# BareBones_Arduino_full_size.net
KiCad netlist of a schematic drawn in EAGLE
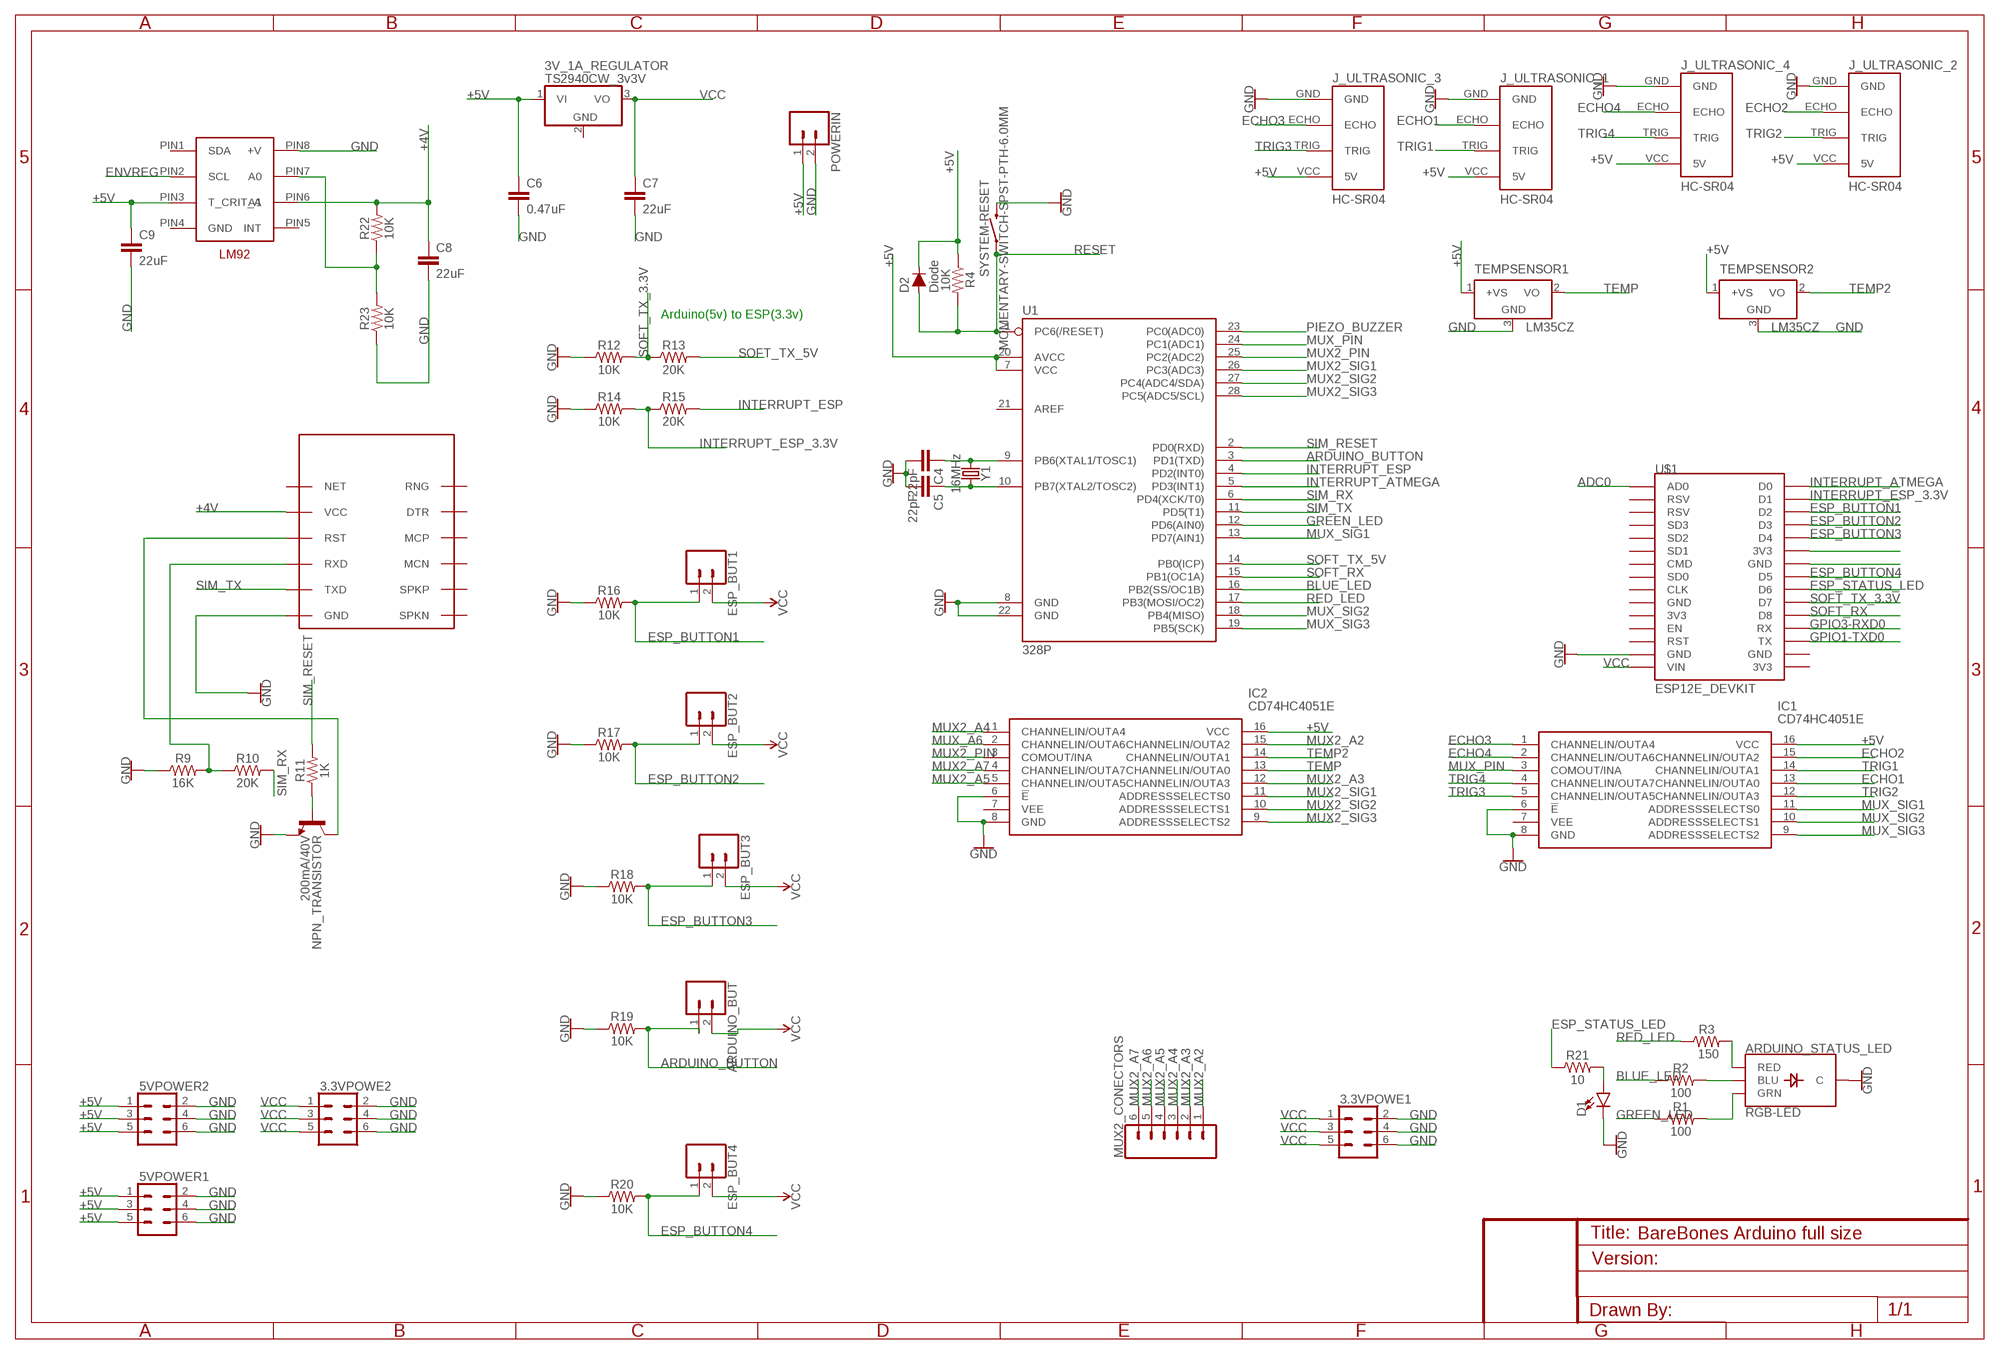
[diagram p0: schematic, sheet 1]

(export (version "E")
  (design (tool "Eeschema 10.0.6"))
  (components
    (comp (ref "3.3VPOWE1")
      (value "CONN_03X2FEMALE")
      (footprint "eagle-import:2X3")
      (libsource (lib "eagle-import") (part "CONN_03X2FEMALE"))
    )
    (comp (ref "3.3VPOWE2")
      (value "CONN_03X2FEMALE")
      (footprint "eagle-import:2X3")
      (libsource (lib "eagle-import") (part "CONN_03X2FEMALE"))
    )
    (comp (ref "3V_1A_REGULATOR")
      (value "TS2940CW_3v3V")
      (footprint "eagle-import:SOT223")
      (libsource (lib "eagle-import") (part "MCP1703DB"))
    )
    (comp (ref "5VPOWER1")
      (value "CONN_03X2FEMALE")
      (footprint "eagle-import:2X3")
      (libsource (lib "eagle-import") (part "CONN_03X2FEMALE"))
    )
    (comp (ref "5VPOWER2")
      (value "CONN_03X2FEMALE")
      (footprint "eagle-import:2X3")
      (libsource (lib "eagle-import") (part "CONN_03X2FEMALE"))
    )
    (comp (ref "ARDUINO_BUT")
      (value "CONN_02")
      (footprint "eagle-import:1X02")
      (libsource (lib "eagle-import") (part "CONN_02"))
    )
    (comp (ref "ARDUINO_STATUS_LED")
      (value "RGB-LED")
      (footprint "eagle-import:LED-RGB-THRU")
      (libsource (lib "eagle-import") (part "LED-RGB-CCDIFFUSE"))
    )
    (comp (ref "C4")
      (value "22pF")
      (footprint "eagle-import:CAP-PTH-2.54")
      (libsource (lib "eagle-import") (part "22PF-PTH-2.54MM-200V-5%"))
    )
    (comp (ref "C5")
      (value "22pF")
      (footprint "eagle-import:CAP-PTH-2.54")
      (libsource (lib "eagle-import") (part "22PF-PTH-2.54MM-200V-5%"))
    )
    (comp (ref "C6")
      (value "0.47uF")
      (footprint "eagle-import:CAP-PTH-SMALL-KIT")
      (libsource (lib "eagle-import") (part "0.1UF-KIT-EZ-50V-20%"))
    )
    (comp (ref "C7")
      (value "22uF")
      (footprint "eagle-import:CAP-PTH-SMALL-KIT")
      (libsource (lib "eagle-import") (part "0.1UF-KIT-EZ-50V-20%"))
    )
    (comp (ref "C8")
      (value "22uF")
      (footprint "eagle-import:CAP-PTH-SMALL-KIT")
      (libsource (lib "eagle-import") (part "0.1UF-KIT-EZ-50V-20%"))
    )
    (comp (ref "C9")
      (value "22uF")
      (footprint "eagle-import:CAP-PTH-SMALL-KIT")
      (libsource (lib "eagle-import") (part "0.1UF-KIT-EZ-50V-20%"))
    )
    (comp (ref "D1")
      (value "LED5MM")
      (footprint "eagle-import:LED_5MM")
      (libsource (lib "eagle-import") (part "LED5MM"))
    )
    (comp (ref "D2")
      (value "Diode")
      (footprint "eagle-import:DIODE-1N4148")
      (libsource (lib "eagle-import") (part "DIODE-1N4148"))
    )
    (comp (ref "ESP_BUT1")
      (value "CONN_02")
      (footprint "eagle-import:1X02")
      (libsource (lib "eagle-import") (part "CONN_02"))
    )
    (comp (ref "ESP_BUT2")
      (value "CONN_02")
      (footprint "eagle-import:1X02")
      (libsource (lib "eagle-import") (part "CONN_02"))
    )
    (comp (ref "ESP_BUT3")
      (value "CONN_02")
      (footprint "eagle-import:1X02")
      (libsource (lib "eagle-import") (part "CONN_02"))
    )
    (comp (ref "ESP_BUT4")
      (value "CONN_02")
      (footprint "eagle-import:1X02")
      (libsource (lib "eagle-import") (part "CONN_02"))
    )
    (comp (ref "IC1")
      (value "CD74HC4051E")
      (footprint "eagle-import:DIP794W53P254L1930H508Q16N")
      (fields (field (name "RS_PART_NUMBER") "2508240054"))
      (libsource (lib "eagle-import") (part "CD74HC4051E"))
    )
    (comp (ref "IC2")
      (value "CD74HC4051E")
      (footprint "eagle-import:DIP794W53P254L1930H508Q16N")
      (fields (field (name "RS_PART_NUMBER") "2508240054"))
      (libsource (lib "eagle-import") (part "CD74HC4051E"))
    )
    (comp (ref "J_ULTRASONIC_1")
      (value "HC-SR04")
      (footprint "eagle-import:HC-SR04_FOOTPRINT")
      (libsource (lib "eagle-import") (part "HC-SR04"))
    )
    (comp (ref "J_ULTRASONIC_2")
      (value "HC-SR04")
      (footprint "eagle-import:HC-SR04_FOOTPRINT")
      (libsource (lib "eagle-import") (part "HC-SR04"))
    )
    (comp (ref "J_ULTRASONIC_3")
      (value "HC-SR04")
      (footprint "eagle-import:HC-SR04_FOOTPRINT")
      (libsource (lib "eagle-import") (part "HC-SR04"))
    )
    (comp (ref "J_ULTRASONIC_4")
      (value "HC-SR04")
      (footprint "eagle-import:HC-SR04_FOOTPRINT")
      (libsource (lib "eagle-import") (part "HC-SR04"))
    )
    (comp (ref "MUX2_CONECTORS")
      (value "CONN_06SILK_FEMALE_PTH")
      (footprint "eagle-import:1X06")
      (libsource (lib "eagle-import") (part "CONN_06SILK_FEMALE_PTH"))
    )
    (comp (ref "NPN_TRANSISTOR")
      (value "200mA/40V")
      (footprint "eagle-import:TO-92")
      (libsource (lib "eagle-import") (part "TRANS_NPN-2N3904"))
    )
    (comp (ref "POWERIN")
      (value "CONN_025MM")
      (footprint "eagle-import:SCREWTERMINAL-5MM-2")
      (libsource (lib "eagle-import") (part "CONN_025MM"))
    )
    (comp (ref "R1")
      (value "100")
      (footprint "eagle-import:AXIAL-0.3")
      (libsource (lib "eagle-import") (part "100OHM-HORIZ-1/4W-1%"))
    )
    (comp (ref "R2")
      (value "100")
      (footprint "eagle-import:AXIAL-0.3")
      (libsource (lib "eagle-import") (part "100OHM-HORIZ-1/4W-1%"))
    )
    (comp (ref "R3")
      (value "150")
      (footprint "eagle-import:AXIAL-0.3")
      (libsource (lib "eagle-import") (part "RESISTORAXIAL-0.3"))
    )
    (comp (ref "R4")
      (value "10K")
      (footprint "eagle-import:AXIAL-0.3")
      (libsource (lib "eagle-import") (part "100OHM-HORIZ-1/4W-1%"))
    )
    (comp (ref "R9")
      (value "16K")
      (footprint "eagle-import:AXIAL-0.3")
      (libsource (lib "eagle-import") (part "100OHM-HORIZ-1/4W-1%"))
    )
    (comp (ref "R10")
      (value "20K")
      (footprint "eagle-import:AXIAL-0.3")
      (libsource (lib "eagle-import") (part "100OHM-HORIZ-1/4W-1%"))
    )
    (comp (ref "R11")
      (value "1K")
      (footprint "eagle-import:AXIAL-0.3")
      (libsource (lib "eagle-import") (part "100OHM-HORIZ-1/4W-1%"))
    )
    (comp (ref "R12")
      (value "10K")
      (footprint "eagle-import:AXIAL-0.3")
      (libsource (lib "eagle-import") (part "100OHM-HORIZ-1/4W-1%"))
    )
    (comp (ref "R13")
      (value "20K")
      (footprint "eagle-import:AXIAL-0.3")
      (libsource (lib "eagle-import") (part "100OHM-HORIZ-1/4W-1%"))
    )
    (comp (ref "R14")
      (value "10K")
      (footprint "eagle-import:AXIAL-0.3")
      (libsource (lib "eagle-import") (part "100OHM-HORIZ-1/4W-1%"))
    )
    (comp (ref "R15")
      (value "20K")
      (footprint "eagle-import:AXIAL-0.3")
      (libsource (lib "eagle-import") (part "100OHM-HORIZ-1/4W-1%"))
    )
    (comp (ref "R16")
      (value "10K")
      (footprint "eagle-import:AXIAL-0.3")
      (libsource (lib "eagle-import") (part "100OHM-HORIZ-1/4W-1%"))
    )
    (comp (ref "R17")
      (value "10K")
      (footprint "eagle-import:AXIAL-0.3")
      (libsource (lib "eagle-import") (part "100OHM-HORIZ-1/4W-1%"))
    )
    (comp (ref "R18")
      (value "10K")
      (footprint "eagle-import:AXIAL-0.3")
      (libsource (lib "eagle-import") (part "100OHM-HORIZ-1/4W-1%"))
    )
    (comp (ref "R19")
      (value "10K")
      (footprint "eagle-import:AXIAL-0.3")
      (libsource (lib "eagle-import") (part "100OHM-HORIZ-1/4W-1%"))
    )
    (comp (ref "R20")
      (value "10K")
      (footprint "eagle-import:AXIAL-0.3")
      (libsource (lib "eagle-import") (part "100OHM-HORIZ-1/4W-1%"))
    )
    (comp (ref "R21")
      (value "10")
      (footprint "eagle-import:AXIAL-0.3")
      (libsource (lib "eagle-import") (part "RESISTORAXIAL-0.3"))
    )
    (comp (ref "R22")
      (value "10K")
      (footprint "eagle-import:AXIAL-0.3")
      (libsource (lib "eagle-import") (part "100OHM-HORIZ-1/4W-1%"))
    )
    (comp (ref "R23")
      (value "10K")
      (footprint "eagle-import:AXIAL-0.3")
      (libsource (lib "eagle-import") (part "100OHM-HORIZ-1/4W-1%"))
    )
    (comp (ref "SYSTEM-RESET")
      (value "MOMENTARY-SWITCH-SPST-PTH-6.0MM")
      (footprint "eagle-import:TACTILE_SWITCH_PTH_6.0MM")
      (libsource (lib "eagle-import") (part "MOMENTARY-SWITCH-SPST-PTH-6.0MM"))
    )
    (comp (ref "TEMPSENSOR1")
      (value "LM35CZ")
      (footprint "eagle-import:TO92")
      (libsource (lib "eagle-import") (part "LM35CZ"))
    )
    (comp (ref "TEMPSENSOR2")
      (value "LM35CZ")
      (footprint "eagle-import:TO92")
      (libsource (lib "eagle-import") (part "LM35CZ"))
    )
    (comp (ref "U$1")
      (value "ESP12E_DEVKIT")
      (footprint "eagle-import:ESP12E_DEVKIT")
      (libsource (lib "eagle-import") (part "ESP12E_DEVKIT"))
    )
    (comp (ref "U$4")
      (value "SIM800L")
      (footprint "eagle-import:SIM-CORE")
      (libsource (lib "eagle-import") (part "SIM800L"))
    )
    (comp (ref "U1")
      (value "328P")
      (footprint "eagle-import:DIP28")
      (libsource (lib "eagle-import") (part "ATMEGA328P_PDIP"))
    )
    (comp (ref "VREG")
      (value "LM92")
      (footprint "eagle-import:SOP-8")
      (fields (field (name "SPICEPREFIX") "X"))
      (libsource (lib "eagle-import") (part "LM92"))
    )
    (comp (ref "Y1")
      (value "16MHz")
      (footprint "eagle-import:HC49US")
      (libsource (lib "eagle-import") (part "CRYSTAL-16MHZPTH-HC49US"))
    )
  )
  (nets
    (net (code "1") (name "/+4V") (class "Default")
      (node (ref "C8") (pin "1") (pinfunction "1_1") (pintype "passive"))
      (node (ref "R22") (pin "P$2") (pinfunction "2_P$2") (pintype "passive"))
      (node (ref "U$4") (pin "VCC") (pinfunction "VCC_VCC") (pintype "bidirectional"))
      (node (ref "VREG") (pin "PIN6") (pinfunction "A1_PIN6") (pintype "bidirectional"))
    )
    (net (code "2") (name "/+5V") (class "Default")
      (node (ref "3V_1A_REGULATOR") (pin "1") (pinfunction "VI_1") (pintype "input"))
      (node (ref "5VPOWER1") (pin "1") (pinfunction "1_1") (pintype "bidirectional"))
      (node (ref "5VPOWER1") (pin "3") (pinfunction "3_3") (pintype "bidirectional"))
      (node (ref "5VPOWER1") (pin "5") (pinfunction "5_5") (pintype "bidirectional"))
      (node (ref "5VPOWER2") (pin "1") (pinfunction "1_1") (pintype "bidirectional"))
      (node (ref "5VPOWER2") (pin "3") (pinfunction "3_3") (pintype "bidirectional"))
      (node (ref "5VPOWER2") (pin "5") (pinfunction "5_5") (pintype "bidirectional"))
      (node (ref "C6") (pin "1") (pinfunction "1_1") (pintype "passive"))
      (node (ref "C9") (pin "1") (pinfunction "1_1") (pintype "passive"))
      (node (ref "D2") (pin "C") (pinfunction "C_C") (pintype "passive"))
      (node (ref "IC1") (pin "16") (pinfunction "VCC_16") (pintype "input"))
      (node (ref "IC2") (pin "16") (pinfunction "VCC_16") (pintype "input"))
      (node (ref "J_ULTRASONIC_1") (pin "VCC") (pinfunction "5V_VCC") (pintype "bidirectional"))
      (node (ref "J_ULTRASONIC_2") (pin "VCC") (pinfunction "5V_VCC") (pintype "bidirectional"))
      (node (ref "J_ULTRASONIC_3") (pin "VCC") (pinfunction "5V_VCC") (pintype "bidirectional"))
      (node (ref "J_ULTRASONIC_4") (pin "VCC") (pinfunction "5V_VCC") (pintype "bidirectional"))
      (node (ref "POWERIN") (pin "1") (pinfunction "1_1") (pintype "passive"))
      (node (ref "R4") (pin "P$1") (pinfunction "1_P$1") (pintype "passive"))
      (node (ref "TEMPSENSOR1") (pin "1") (pinfunction "+VS_1") (pintype "input"))
      (node (ref "TEMPSENSOR2") (pin "1") (pinfunction "+VS_1") (pintype "input"))
      (node (ref "U1") (pin "20") (pinfunction "AVCC_20") (pintype "bidirectional"))
      (node (ref "U1") (pin "7") (pinfunction "VCC_7") (pintype "bidirectional"))
      (node (ref "VREG") (pin "PIN3") (pinfunction "T_CRIT_A_PIN3") (pintype "bidirectional"))
    )
    (net (code "3") (name "/ADC0") (class "Default")
      (node (ref "U$1") (pin "AD0") (pinfunction "AD0_AD0") (pintype "bidirectional"))
    )
    (net (code "4") (name "/ARDUINO_BUTTON") (class "Default")
      (node (ref "ARDUINO_BUT") (pin "1") (pinfunction "1_1") (pintype "passive"))
      (node (ref "R19") (pin "P$2") (pinfunction "2_P$2") (pintype "passive"))
      (node (ref "U1") (pin "3") (pinfunction "PD1(TXD)_3") (pintype "bidirectional"))
    )
    (net (code "5") (name "/BLUE_LED") (class "Default")
      (node (ref "R2") (pin "P$1") (pinfunction "1_P$1") (pintype "passive"))
      (node (ref "U1") (pin "16") (pinfunction "PB2(SS/OC1B)_16") (pintype "bidirectional"))
    )
    (net (code "6") (name "/ECHO1") (class "Default")
      (node (ref "IC1") (pin "13") (pinfunction "CHANNELIN/OUTA0_13") (pintype "input"))
      (node (ref "J_ULTRASONIC_1") (pin "ECHO") (pinfunction "ECHO_ECHO") (pintype "bidirectional"))
    )
    (net (code "7") (name "/ECHO2") (class "Default")
      (node (ref "IC1") (pin "15") (pinfunction "CHANNELIN/OUTA2_15") (pintype "input"))
      (node (ref "J_ULTRASONIC_2") (pin "ECHO") (pinfunction "ECHO_ECHO") (pintype "bidirectional"))
    )
    (net (code "8") (name "/ECHO3") (class "Default")
      (node (ref "IC1") (pin "1") (pinfunction "CHANNELIN/OUTA4_1") (pintype "input"))
      (node (ref "J_ULTRASONIC_3") (pin "ECHO") (pinfunction "ECHO_ECHO") (pintype "bidirectional"))
    )
    (net (code "9") (name "/ECHO4") (class "Default")
      (node (ref "IC1") (pin "2") (pinfunction "CHANNELIN/OUTA6_2") (pintype "input"))
      (node (ref "J_ULTRASONIC_4") (pin "ECHO") (pinfunction "ECHO_ECHO") (pintype "bidirectional"))
    )
    (net (code "10") (name "/ENVREG") (class "Default")
      (node (ref "VREG") (pin "PIN2") (pinfunction "SCL_PIN2") (pintype "bidirectional"))
    )
    (net (code "11") (name "/ESP_BUTTON1") (class "Default")
      (node (ref "ESP_BUT1") (pin "1") (pinfunction "1_1") (pintype "passive"))
      (node (ref "R16") (pin "P$2") (pinfunction "2_P$2") (pintype "passive"))
      (node (ref "U$1") (pin "D2") (pinfunction "D2_D2") (pintype "bidirectional"))
    )
    (net (code "12") (name "/ESP_BUTTON2") (class "Default")
      (node (ref "ESP_BUT2") (pin "1") (pinfunction "1_1") (pintype "passive"))
      (node (ref "R17") (pin "P$2") (pinfunction "2_P$2") (pintype "passive"))
      (node (ref "U$1") (pin "D3") (pinfunction "D3_D3") (pintype "bidirectional"))
    )
    (net (code "13") (name "/ESP_BUTTON3") (class "Default")
      (node (ref "ESP_BUT3") (pin "1") (pinfunction "1_1") (pintype "passive"))
      (node (ref "R18") (pin "P$2") (pinfunction "2_P$2") (pintype "passive"))
      (node (ref "U$1") (pin "D4") (pinfunction "D4_D4") (pintype "bidirectional"))
    )
    (net (code "14") (name "/ESP_BUTTON4") (class "Default")
      (node (ref "ESP_BUT4") (pin "1") (pinfunction "1_1") (pintype "passive"))
      (node (ref "R20") (pin "P$2") (pinfunction "2_P$2") (pintype "passive"))
      (node (ref "U$1") (pin "D5") (pinfunction "D5_D5") (pintype "bidirectional"))
    )
    (net (code "15") (name "/ESP_STATUS_LED") (class "Default")
      (node (ref "R21") (pin "P$1") (pinfunction "1_P$1") (pintype "passive"))
      (node (ref "U$1") (pin "D6") (pinfunction "D6_D6") (pintype "bidirectional"))
    )
    (net (code "16") (name "/GPIO1-TXD0") (class "Default")
      (node (ref "U$1") (pin "TX") (pinfunction "TX_TX") (pintype "bidirectional"))
    )
    (net (code "17") (name "/GPIO3-RXD0") (class "Default")
      (node (ref "U$1") (pin "RX") (pinfunction "RX_RX") (pintype "bidirectional"))
    )
    (net (code "18") (name "/GREEN_LED") (class "Default")
      (node (ref "R1") (pin "P$1") (pinfunction "1_P$1") (pintype "passive"))
      (node (ref "U1") (pin "12") (pinfunction "PD6(AIN0)_12") (pintype "bidirectional"))
    )
    (net (code "19") (name "/INTERRUPT_ATMEGA") (class "Default")
      (node (ref "U$1") (pin "D0") (pinfunction "D0_D0") (pintype "bidirectional"))
      (node (ref "U1") (pin "5") (pinfunction "PD3(INT1)_5") (pintype "bidirectional"))
    )
    (net (code "20") (name "/INTERRUPT_ESP") (class "Default")
      (node (ref "R15") (pin "P$2") (pinfunction "2_P$2") (pintype "passive"))
      (node (ref "U1") (pin "4") (pinfunction "PD2(INT0)_4") (pintype "bidirectional"))
    )
    (net (code "21") (name "/INTERRUPT_ESP_3.3V") (class "Default")
      (node (ref "R14") (pin "P$2") (pinfunction "2_P$2") (pintype "passive"))
      (node (ref "R15") (pin "P$1") (pinfunction "1_P$1") (pintype "passive"))
      (node (ref "U$1") (pin "D1") (pinfunction "D1_D1") (pintype "bidirectional"))
    )
    (net (code "22") (name "/MUX2_A2") (class "Default")
      (node (ref "IC2") (pin "15") (pinfunction "CHANNELIN/OUTA2_15") (pintype "input"))
      (node (ref "MUX2_CONECTORS") (pin "1") (pinfunction "1_1") (pintype "passive"))
    )
    (net (code "23") (name "/MUX2_A3") (class "Default")
      (node (ref "IC2") (pin "12") (pinfunction "CHANNELIN/OUTA3_12") (pintype "input"))
      (node (ref "MUX2_CONECTORS") (pin "2") (pinfunction "2_2") (pintype "passive"))
    )
    (net (code "24") (name "/MUX2_A4") (class "Default")
      (node (ref "IC2") (pin "1") (pinfunction "CHANNELIN/OUTA4_1") (pintype "input"))
      (node (ref "MUX2_CONECTORS") (pin "3") (pinfunction "3_3") (pintype "passive"))
    )
    (net (code "25") (name "/MUX2_A5") (class "Default")
      (node (ref "IC2") (pin "5") (pinfunction "CHANNELIN/OUTA5_5") (pintype "input"))
      (node (ref "MUX2_CONECTORS") (pin "4") (pinfunction "4_4") (pintype "passive"))
    )
    (net (code "26") (name "/MUX2_A6") (class "Default")
      (node (ref "MUX2_CONECTORS") (pin "5") (pinfunction "5_5") (pintype "passive"))
    )
    (net (code "27") (name "/MUX2_A7") (class "Default")
      (node (ref "IC2") (pin "4") (pinfunction "CHANNELIN/OUTA7_4") (pintype "input"))
      (node (ref "MUX2_CONECTORS") (pin "6") (pinfunction "6_6") (pintype "passive"))
    )
    (net (code "28") (name "/MUX2_PIN") (class "Default")
      (node (ref "IC2") (pin "3") (pinfunction "COMOUT/INA_3") (pintype "input"))
      (node (ref "U1") (pin "25") (pinfunction "PC2(ADC2)_25") (pintype "bidirectional"))
    )
    (net (code "29") (name "/MUX2_SIG1") (class "Default")
      (node (ref "IC2") (pin "11") (pinfunction "ADDRESSSELECTS0_11") (pintype "input"))
      (node (ref "U1") (pin "26") (pinfunction "PC3(ADC3)_26") (pintype "bidirectional"))
    )
    (net (code "30") (name "/MUX2_SIG2") (class "Default")
      (node (ref "IC2") (pin "10") (pinfunction "ADDRESSSELECTS1_10") (pintype "input"))
      (node (ref "U1") (pin "27") (pinfunction "PC4(ADC4/SDA)_27") (pintype "bidirectional"))
    )
    (net (code "31") (name "/MUX2_SIG3") (class "Default")
      (node (ref "IC2") (pin "9") (pinfunction "ADDRESSSELECTS2_9") (pintype "input"))
      (node (ref "U1") (pin "28") (pinfunction "PC5(ADC5/SCL)_28") (pintype "bidirectional"))
    )
    (net (code "32") (name "/MUX_A6") (class "Default")
      (node (ref "IC2") (pin "2") (pinfunction "CHANNELIN/OUTA6_2") (pintype "input"))
    )
    (net (code "33") (name "/MUX_PIN") (class "Default")
      (node (ref "IC1") (pin "3") (pinfunction "COMOUT/INA_3") (pintype "input"))
      (node (ref "U1") (pin "24") (pinfunction "PC1(ADC1)_24") (pintype "bidirectional"))
    )
    (net (code "34") (name "/MUX_SIG1") (class "Default")
      (node (ref "IC1") (pin "11") (pinfunction "ADDRESSSELECTS0_11") (pintype "input"))
      (node (ref "U1") (pin "13") (pinfunction "PD7(AIN1)_13") (pintype "bidirectional"))
    )
    (net (code "35") (name "/MUX_SIG2") (class "Default")
      (node (ref "IC1") (pin "10") (pinfunction "ADDRESSSELECTS1_10") (pintype "input"))
      (node (ref "U1") (pin "18") (pinfunction "PB4(MISO)_18") (pintype "bidirectional"))
    )
    (net (code "36") (name "/MUX_SIG3") (class "Default")
      (node (ref "IC1") (pin "9") (pinfunction "ADDRESSSELECTS2_9") (pintype "input"))
      (node (ref "U1") (pin "19") (pinfunction "PB5(SCK)_19") (pintype "bidirectional"))
    )
    (net (code "37") (name "/PIEZO_BUZZER") (class "Default")
      (node (ref "U1") (pin "23") (pinfunction "PC0(ADC0)_23") (pintype "bidirectional"))
    )
    (net (code "38") (name "/RED_LED") (class "Default")
      (node (ref "R3") (pin "P$1") (pinfunction "1_P$1") (pintype "passive"))
      (node (ref "U1") (pin "17") (pinfunction "PB3(MOSI/OC2)_17") (pintype "bidirectional"))
    )
    (net (code "39") (name "/RESET") (class "Default")
      (node (ref "D2") (pin "A") (pinfunction "A_A") (pintype "passive"))
      (node (ref "R4") (pin "P$2") (pinfunction "2_P$2") (pintype "passive"))
      (node (ref "SYSTEM-RESET") (pin "1") (pinfunction "1_1") (pintype "passive"))
      (node (ref "U1") (pin "1") (pinfunction "PC6(/RESET)_1") (pintype "bidirectional"))
    )
    (net (code "40") (name "/SIM_RESET") (class "Default")
      (node (ref "R11") (pin "P$2") (pinfunction "2_P$2") (pintype "passive"))
      (node (ref "U1") (pin "2") (pinfunction "PD0(RXD)_2") (pintype "bidirectional"))
    )
    (net (code "41") (name "/SIM_RX") (class "Default")
      (node (ref "R10") (pin "P$2") (pinfunction "2_P$2") (pintype "passive"))
      (node (ref "U1") (pin "6") (pinfunction "PD4(XCK/T0)_6") (pintype "bidirectional"))
    )
    (net (code "42") (name "/SIM_TX") (class "Default")
      (node (ref "U$4") (pin "TXD") (pinfunction "TXD_TXD") (pintype "bidirectional"))
      (node (ref "U1") (pin "11") (pinfunction "PD5(T1)_11") (pintype "bidirectional"))
    )
    (net (code "43") (name "/SOFT_RX") (class "Default")
      (node (ref "U$1") (pin "D8") (pinfunction "D8_D8") (pintype "bidirectional"))
      (node (ref "U1") (pin "15") (pinfunction "PB1(OC1A)_15") (pintype "bidirectional"))
    )
    (net (code "44") (name "/SOFT_TX_3.3V") (class "Default")
      (node (ref "R12") (pin "P$2") (pinfunction "2_P$2") (pintype "passive"))
      (node (ref "R13") (pin "P$1") (pinfunction "1_P$1") (pintype "passive"))
      (node (ref "U$1") (pin "D7") (pinfunction "D7_D7") (pintype "bidirectional"))
    )
    (net (code "45") (name "/SOFT_TX_5V") (class "Default")
      (node (ref "R13") (pin "P$2") (pinfunction "2_P$2") (pintype "passive"))
      (node (ref "U1") (pin "14") (pinfunction "PB0(ICP)_14") (pintype "bidirectional"))
    )
    (net (code "46") (name "/TEMP") (class "Default")
      (node (ref "IC2") (pin "13") (pinfunction "CHANNELIN/OUTA0_13") (pintype "input"))
      (node (ref "TEMPSENSOR1") (pin "2") (pinfunction "VO_2") (pintype "input"))
    )
    (net (code "47") (name "/TEMP2") (class "Default")
      (node (ref "IC2") (pin "14") (pinfunction "CHANNELIN/OUTA1_14") (pintype "input"))
      (node (ref "TEMPSENSOR2") (pin "2") (pinfunction "VO_2") (pintype "input"))
    )
    (net (code "48") (name "/TRIG1") (class "Default")
      (node (ref "IC1") (pin "14") (pinfunction "CHANNELIN/OUTA1_14") (pintype "input"))
      (node (ref "J_ULTRASONIC_1") (pin "TRIG") (pinfunction "TRIG_TRIG") (pintype "bidirectional"))
    )
    (net (code "49") (name "/TRIG2") (class "Default")
      (node (ref "IC1") (pin "12") (pinfunction "CHANNELIN/OUTA3_12") (pintype "input"))
      (node (ref "J_ULTRASONIC_2") (pin "TRIG") (pinfunction "TRIG_TRIG") (pintype "bidirectional"))
    )
    (net (code "50") (name "/TRIG3") (class "Default")
      (node (ref "IC1") (pin "5") (pinfunction "CHANNELIN/OUTA5_5") (pintype "input"))
      (node (ref "J_ULTRASONIC_3") (pin "TRIG") (pinfunction "TRIG_TRIG") (pintype "bidirectional"))
    )
    (net (code "51") (name "/TRIG4") (class "Default")
      (node (ref "IC1") (pin "4") (pinfunction "CHANNELIN/OUTA7_4") (pintype "input"))
      (node (ref "J_ULTRASONIC_4") (pin "TRIG") (pinfunction "TRIG_TRIG") (pintype "bidirectional"))
    )
    (net (code "52") (name "GND") (class "Default")
      (node (ref "3.3VPOWE1") (pin "2") (pinfunction "2_2") (pintype "bidirectional"))
      (node (ref "3.3VPOWE1") (pin "4") (pinfunction "4_4") (pintype "bidirectional"))
      (node (ref "3.3VPOWE1") (pin "6") (pinfunction "6_6") (pintype "bidirectional"))
      (node (ref "3.3VPOWE2") (pin "2") (pinfunction "2_2") (pintype "bidirectional"))
      (node (ref "3.3VPOWE2") (pin "4") (pinfunction "4_4") (pintype "bidirectional"))
      (node (ref "3.3VPOWE2") (pin "6") (pinfunction "6_6") (pintype "bidirectional"))
      (node (ref "5VPOWER1") (pin "2") (pinfunction "2_2") (pintype "bidirectional"))
      (node (ref "5VPOWER1") (pin "4") (pinfunction "4_4") (pintype "bidirectional"))
      (node (ref "5VPOWER1") (pin "6") (pinfunction "6_6") (pintype "bidirectional"))
      (node (ref "5VPOWER2") (pin "2") (pinfunction "2_2") (pintype "bidirectional"))
      (node (ref "5VPOWER2") (pin "4") (pinfunction "4_4") (pintype "bidirectional"))
      (node (ref "5VPOWER2") (pin "6") (pinfunction "6_6") (pintype "bidirectional"))
      (node (ref "ARDUINO_STATUS_LED") (pin "2") (pinfunction "C_2") (pintype "bidirectional"))
      (node (ref "C4") (pin "2") (pinfunction "2_2") (pintype "passive"))
      (node (ref "C5") (pin "2") (pinfunction "2_2") (pintype "passive"))
      (node (ref "C6") (pin "2") (pinfunction "2_2") (pintype "passive"))
      (node (ref "C7") (pin "2") (pinfunction "2_2") (pintype "passive"))
      (node (ref "C8") (pin "2") (pinfunction "2_2") (pintype "passive"))
      (node (ref "C9") (pin "2") (pinfunction "2_2") (pintype "passive"))
      (node (ref "D1") (pin "K") (pinfunction "C_K") (pintype "passive"))
      (node (ref "IC1") (pin "6") (pinfunction "~{E}_6") (pintype "input"))
      (node (ref "IC1") (pin "8") (pinfunction "GND_8") (pintype "input"))
      (node (ref "IC2") (pin "6") (pinfunction "~{E}_6") (pintype "input"))
      (node (ref "IC2") (pin "8") (pinfunction "GND_8") (pintype "input"))
      (node (ref "J_ULTRASONIC_1") (pin "GND") (pinfunction "GND_GND") (pintype "bidirectional"))
      (node (ref "J_ULTRASONIC_2") (pin "GND") (pinfunction "GND_GND") (pintype "bidirectional"))
      (node (ref "J_ULTRASONIC_3") (pin "GND") (pinfunction "GND_GND") (pintype "bidirectional"))
      (node (ref "J_ULTRASONIC_4") (pin "GND") (pinfunction "GND_GND") (pintype "bidirectional"))
      (node (ref "NPN_TRANSISTOR") (pin "1") (pinfunction "E_1") (pintype "passive"))
      (node (ref "POWERIN") (pin "2") (pinfunction "2_2") (pintype "passive"))
      (node (ref "R12") (pin "P$1") (pinfunction "1_P$1") (pintype "passive"))
      (node (ref "R14") (pin "P$1") (pinfunction "1_P$1") (pintype "passive"))
      (node (ref "R16") (pin "P$1") (pinfunction "1_P$1") (pintype "passive"))
      (node (ref "R17") (pin "P$1") (pinfunction "1_P$1") (pintype "passive"))
      (node (ref "R18") (pin "P$1") (pinfunction "1_P$1") (pintype "passive"))
      (node (ref "R19") (pin "P$1") (pinfunction "1_P$1") (pintype "passive"))
      (node (ref "R20") (pin "P$1") (pinfunction "1_P$1") (pintype "passive"))
      (node (ref "R23") (pin "P$1") (pinfunction "1_P$1") (pintype "passive"))
      (node (ref "R9") (pin "P$1") (pinfunction "1_P$1") (pintype "passive"))
      (node (ref "SYSTEM-RESET") (pin "3") (pinfunction "2_3") (pintype "passive"))
      (node (ref "TEMPSENSOR1") (pin "3") (pinfunction "GND_3") (pintype "power_in"))
      (node (ref "TEMPSENSOR2") (pin "3") (pinfunction "GND_3") (pintype "power_in"))
      (node (ref "U$1") (pin "GND@1") (pinfunction "GND_GND@1") (pintype "bidirectional"))
      (node (ref "U$4") (pin "GND") (pinfunction "GND_GND") (pintype "bidirectional"))
      (node (ref "U1") (pin "22") (pinfunction "GND_22") (pintype "bidirectional"))
      (node (ref "U1") (pin "8") (pinfunction "GND_8") (pintype "bidirectional"))
      (node (ref "VREG") (pin "PIN8") (pinfunction "+V_PIN8") (pintype "bidirectional"))
    )
    (net (code "53") (name "Net-(ARDUINO_STATUS_LED-BLU)") (class "Default")
      (node (ref "ARDUINO_STATUS_LED") (pin "4") (pinfunction "BLU_4") (pintype "bidirectional"))
      (node (ref "R2") (pin "P$2") (pinfunction "2_P$2") (pintype "passive"))
    )
    (net (code "54") (name "Net-(ARDUINO_STATUS_LED-GRN)") (class "Default")
      (node (ref "ARDUINO_STATUS_LED") (pin "3") (pinfunction "GRN_3") (pintype "bidirectional"))
      (node (ref "R1") (pin "P$2") (pinfunction "2_P$2") (pintype "passive"))
    )
    (net (code "55") (name "Net-(ARDUINO_STATUS_LED-RED)") (class "Default")
      (node (ref "ARDUINO_STATUS_LED") (pin "1") (pinfunction "RED_1") (pintype "bidirectional"))
      (node (ref "R3") (pin "P$2") (pinfunction "2_P$2") (pintype "passive"))
    )
    (net (code "56") (name "Net-(NPN_TRANSISTOR-B)") (class "Default")
      (node (ref "NPN_TRANSISTOR") (pin "2") (pinfunction "B_2") (pintype "passive"))
      (node (ref "R11") (pin "P$1") (pinfunction "1_P$1") (pintype "passive"))
    )
    (net (code "57") (name "Net-(NPN_TRANSISTOR-C)") (class "Default")
      (node (ref "NPN_TRANSISTOR") (pin "3") (pinfunction "C_3") (pintype "passive"))
      (node (ref "U$4") (pin "RST") (pinfunction "RST_RST") (pintype "bidirectional"))
    )
    (net (code "58") (name "Net-(R10-1)") (class "Default")
      (node (ref "R10") (pin "P$1") (pinfunction "1_P$1") (pintype "passive"))
      (node (ref "R9") (pin "P$2") (pinfunction "2_P$2") (pintype "passive"))
      (node (ref "U$4") (pin "RXD") (pinfunction "RXD_RXD") (pintype "bidirectional"))
    )
    (net (code "59") (name "Net-(R21-2)") (class "Default")
      (node (ref "D1") (pin "A") (pinfunction "A_A") (pintype "passive"))
      (node (ref "R21") (pin "P$2") (pinfunction "2_P$2") (pintype "passive"))
    )
    (net (code "60") (name "Net-(R22-1)") (class "Default")
      (node (ref "R22") (pin "P$1") (pinfunction "1_P$1") (pintype "passive"))
      (node (ref "R23") (pin "P$2") (pinfunction "2_P$2") (pintype "passive"))
      (node (ref "VREG") (pin "PIN7") (pinfunction "A0_PIN7") (pintype "bidirectional"))
    )
    (net (code "61") (name "Net-(U1-PB6(XTAL1{slash}TOSC1))") (class "Default")
      (node (ref "C4") (pin "1") (pinfunction "1_1") (pintype "passive"))
      (node (ref "U1") (pin "9") (pinfunction "PB6(XTAL1/TOSC1)_9") (pintype "bidirectional"))
      (node (ref "Y1") (pin "1") (pinfunction "1_1") (pintype "passive"))
    )
    (net (code "62") (name "Net-(U1-PB7(XTAL2{slash}TOSC2))") (class "Default")
      (node (ref "C5") (pin "1") (pinfunction "1_1") (pintype "passive"))
      (node (ref "U1") (pin "10") (pinfunction "PB7(XTAL2/TOSC2)_10") (pintype "bidirectional"))
      (node (ref "Y1") (pin "2") (pinfunction "2_2") (pintype "passive"))
    )
    (net (code "63") (name "VCC") (class "Default")
      (node (ref "3.3VPOWE1") (pin "1") (pinfunction "1_1") (pintype "bidirectional"))
      (node (ref "3.3VPOWE1") (pin "3") (pinfunction "3_3") (pintype "bidirectional"))
      (node (ref "3.3VPOWE1") (pin "5") (pinfunction "5_5") (pintype "bidirectional"))
      (node (ref "3.3VPOWE2") (pin "1") (pinfunction "1_1") (pintype "bidirectional"))
      (node (ref "3.3VPOWE2") (pin "3") (pinfunction "3_3") (pintype "bidirectional"))
      (node (ref "3.3VPOWE2") (pin "5") (pinfunction "5_5") (pintype "bidirectional"))
      (node (ref "3V_1A_REGULATOR") (pin "3") (pinfunction "VO_3") (pintype "passive"))
      (node (ref "ARDUINO_BUT") (pin "2") (pinfunction "2_2") (pintype "passive"))
      (node (ref "C7") (pin "1") (pinfunction "1_1") (pintype "passive"))
      (node (ref "ESP_BUT1") (pin "2") (pinfunction "2_2") (pintype "passive"))
      (node (ref "ESP_BUT2") (pin "2") (pinfunction "2_2") (pintype "passive"))
      (node (ref "ESP_BUT3") (pin "2") (pinfunction "2_2") (pintype "passive"))
      (node (ref "ESP_BUT4") (pin "2") (pinfunction "2_2") (pintype "passive"))
      (node (ref "U$1") (pin "VIN") (pinfunction "VIN_VIN") (pintype "bidirectional"))
    )
    (net (code "64") (name "unconnected-(3V_1A_REGULATOR-GND-Pad2)") (class "Default")
      (node (ref "3V_1A_REGULATOR") (pin "2") (pinfunction "GND_2") (pintype "passive"))
    )
    (net (code "65") (name "unconnected-(IC1-VEE-Pad7)") (class "Default")
      (node (ref "IC1") (pin "7") (pinfunction "VEE_7") (pintype "input"))
    )
    (net (code "66") (name "unconnected-(IC2-VEE-Pad7)") (class "Default")
      (node (ref "IC2") (pin "7") (pinfunction "VEE_7") (pintype "input"))
    )
    (net (code "67") (name "unconnected-(U$1-3V3-Pad3V3@0)") (class "Default")
      (node (ref "U$1") (pin "3V3@0") (pinfunction "3V3_3V3@0") (pintype "bidirectional"))
    )
    (net (code "68") (name "unconnected-(U$1-3V3-Pad3V3@1)") (class "Default")
      (node (ref "U$1") (pin "3V3@1") (pinfunction "3V3_3V3@1") (pintype "bidirectional"))
    )
    (net (code "69") (name "unconnected-(U$1-3V3-Pad3V3@2)") (class "Default")
      (node (ref "U$1") (pin "3V3@2") (pinfunction "3V3_3V3@2") (pintype "bidirectional"))
    )
    (net (code "70") (name "unconnected-(U$1-GND-PadGND@0)") (class "Default")
      (node (ref "U$1") (pin "GND@0") (pinfunction "GND_GND@0") (pintype "bidirectional"))
    )
    (net (code "71") (name "unconnected-(U$1-GND-PadGND@2)") (class "Default")
      (node (ref "U$1") (pin "GND@2") (pinfunction "GND_GND@2") (pintype "bidirectional"))
    )
    (net (code "72") (name "unconnected-(U$1-GND-PadGND@3)") (class "Default")
      (node (ref "U$1") (pin "GND@3") (pinfunction "GND_GND@3") (pintype "bidirectional"))
    )
    (net (code "73") (name "unconnected-(U$1-PadCLK)") (class "Default")
      (node (ref "U$1") (pin "CLK") (pinfunction "CLK_CLK") (pintype "bidirectional"))
    )
    (net (code "74") (name "unconnected-(U$1-PadCMD)") (class "Default")
      (node (ref "U$1") (pin "CMD") (pinfunction "CMD_CMD") (pintype "bidirectional"))
    )
    (net (code "75") (name "unconnected-(U$1-PadEN)") (class "Default")
      (node (ref "U$1") (pin "EN") (pinfunction "EN_EN") (pintype "bidirectional"))
    )
    (net (code "76") (name "unconnected-(U$1-PadRST)") (class "Default")
      (node (ref "U$1") (pin "RST") (pinfunction "RST_RST") (pintype "bidirectional"))
    )
    (net (code "77") (name "unconnected-(U$1-PadSD0)") (class "Default")
      (node (ref "U$1") (pin "SD0") (pinfunction "SD0_SD0") (pintype "bidirectional"))
    )
    (net (code "78") (name "unconnected-(U$1-PadSD1)") (class "Default")
      (node (ref "U$1") (pin "SD1") (pinfunction "SD1_SD1") (pintype "bidirectional"))
    )
    (net (code "79") (name "unconnected-(U$1-PadSD2)") (class "Default")
      (node (ref "U$1") (pin "SD2") (pinfunction "SD2_SD2") (pintype "bidirectional"))
    )
    (net (code "80") (name "unconnected-(U$1-PadSD3)") (class "Default")
      (node (ref "U$1") (pin "SD3") (pinfunction "SD3_SD3") (pintype "bidirectional"))
    )
    (net (code "81") (name "unconnected-(U$1-RSV-PadRSV@0)") (class "Default")
      (node (ref "U$1") (pin "RSV@0") (pinfunction "RSV_RSV@0") (pintype "bidirectional"))
    )
    (net (code "82") (name "unconnected-(U$1-RSV-PadRSV@1)") (class "Default")
      (node (ref "U$1") (pin "RSV@1") (pinfunction "RSV_RSV@1") (pintype "bidirectional"))
    )
    (net (code "83") (name "unconnected-(U$4-PadDTR)") (class "Default")
      (node (ref "U$4") (pin "DTR") (pinfunction "DTR_DTR") (pintype "bidirectional"))
    )
    (net (code "84") (name "unconnected-(U$4-PadMCN)") (class "Default")
      (node (ref "U$4") (pin "MCN") (pinfunction "MCN_MCN") (pintype "bidirectional"))
    )
    (net (code "85") (name "unconnected-(U$4-PadMCP)") (class "Default")
      (node (ref "U$4") (pin "MCP") (pinfunction "MCP_MCP") (pintype "bidirectional"))
    )
    (net (code "86") (name "unconnected-(U$4-PadNET)") (class "Default")
      (node (ref "U$4") (pin "NET") (pinfunction "NET_NET") (pintype "bidirectional"))
    )
    (net (code "87") (name "unconnected-(U$4-PadRNG)") (class "Default")
      (node (ref "U$4") (pin "RNG") (pinfunction "RNG_RNG") (pintype "bidirectional"))
    )
    (net (code "88") (name "unconnected-(U$4-PadSPKN)") (class "Default")
      (node (ref "U$4") (pin "SPKN") (pinfunction "SPKN_SPKN") (pintype "bidirectional"))
    )
    (net (code "89") (name "unconnected-(U$4-PadSPKP)") (class "Default")
      (node (ref "U$4") (pin "SPKP") (pinfunction "SPKP_SPKP") (pintype "bidirectional"))
    )
    (net (code "90") (name "unconnected-(U1-AREF-Pad21)") (class "Default")
      (node (ref "U1") (pin "21") (pinfunction "AREF_21") (pintype "bidirectional"))
    )
    (net (code "91") (name "unconnected-(VREG-GND-PadPIN4)") (class "Default")
      (node (ref "VREG") (pin "PIN4") (pinfunction "GND_PIN4") (pintype "bidirectional"))
    )
    (net (code "92") (name "unconnected-(VREG-INT-PadPIN5)") (class "Default")
      (node (ref "VREG") (pin "PIN5") (pinfunction "INT_PIN5") (pintype "bidirectional"))
    )
    (net (code "93") (name "unconnected-(VREG-SDA-PadPIN1)") (class "Default")
      (node (ref "VREG") (pin "PIN1") (pinfunction "SDA_PIN1") (pintype "bidirectional"))
    )
  )
)
